# 68000_afterWireing.net
KiCad netlist of a schematic drawn in EAGLE
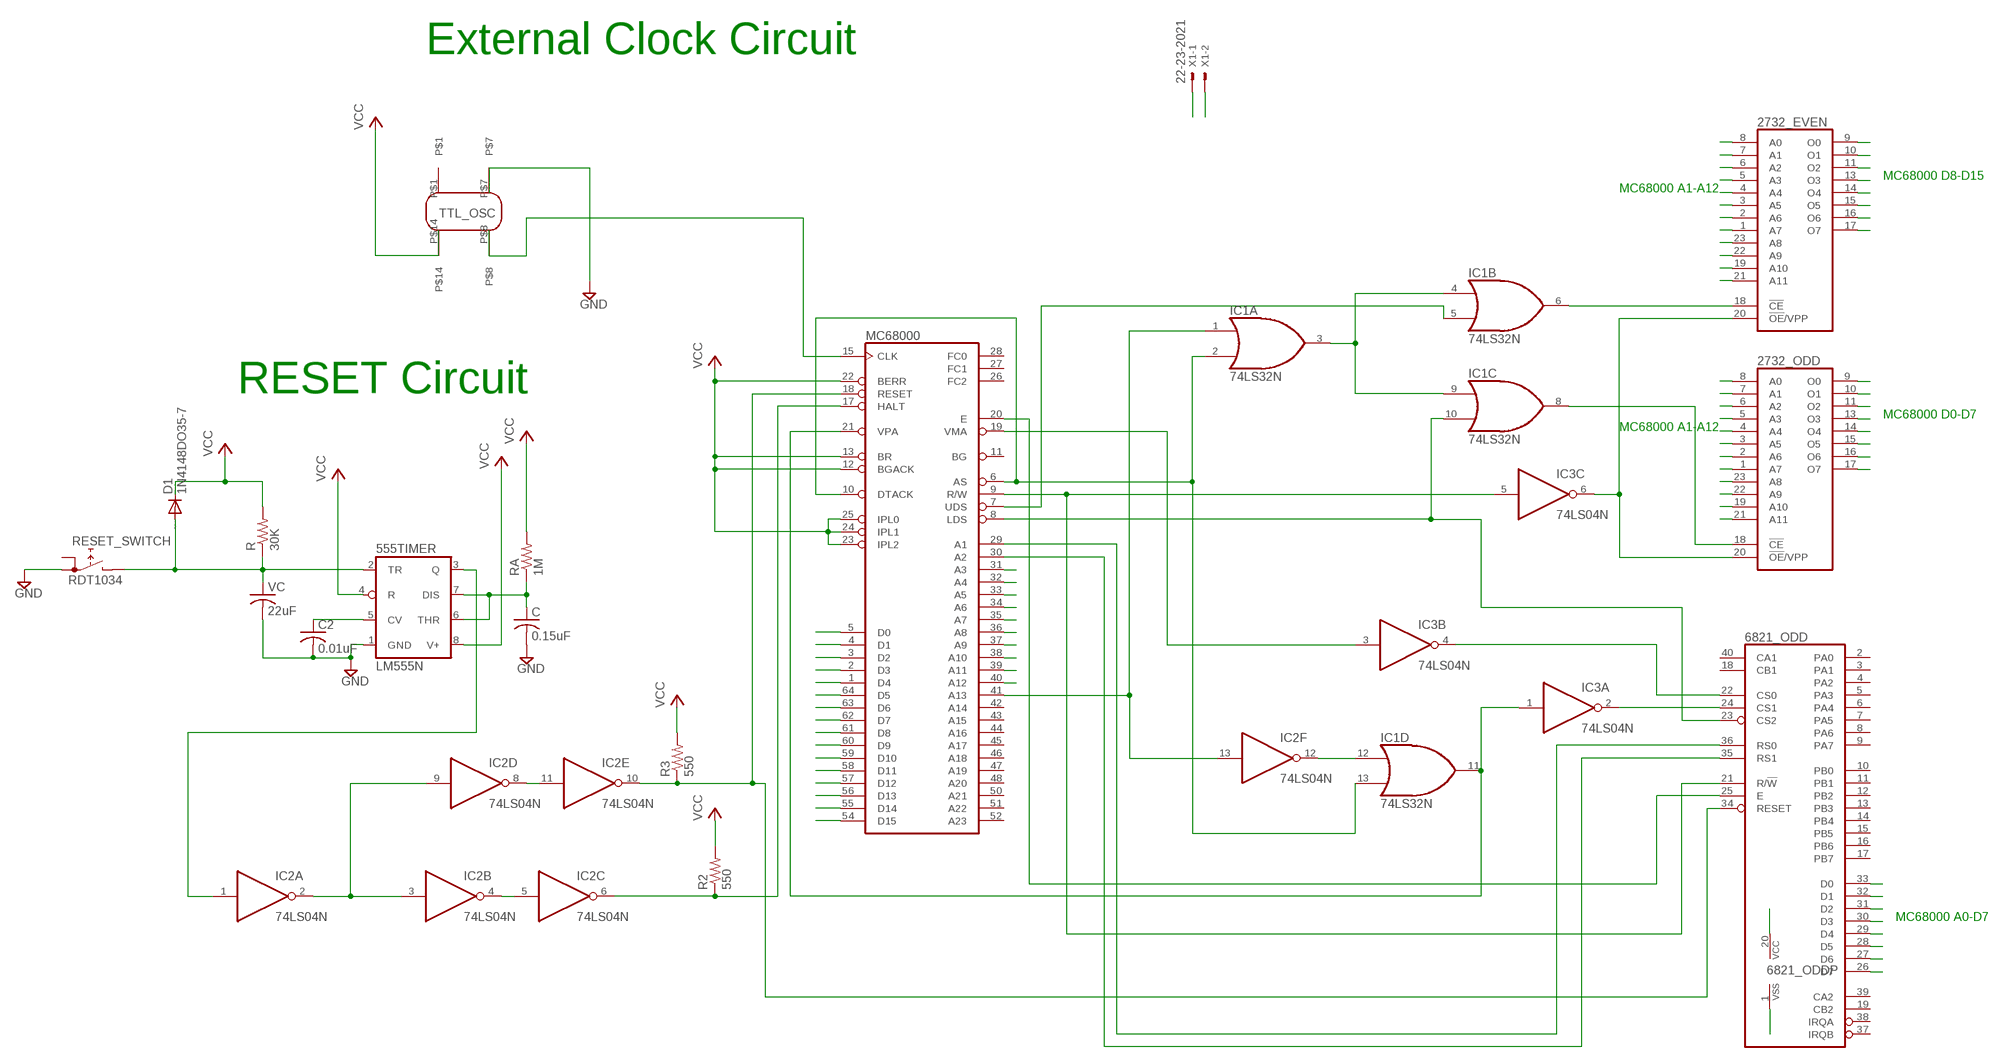
[diagram p0: schematic, sheet 1]

(export (version "E")
  (design (tool "Eeschema 10.0.6"))
  (components
    (comp (ref "555TIMER")
      (value "LM555N")
      (footprint "eagle-import:DIL08")
      (libsource (lib "eagle-import") (part "555NLM"))
    )
    (comp (ref "2732_EVEN")
      (value "2732")
      (footprint "eagle-import:DIL24")
      (libsource (lib "eagle-import") (part "2732"))
    )
    (comp (ref "2732_ODD")
      (value "2732")
      (footprint "eagle-import:DIL24")
      (libsource (lib "eagle-import") (part "2732"))
    )
    (comp (ref "6821_ODD")
      (value "6821")
      (footprint "eagle-import:DIL40")
      (fields (field (name "MF") "NTE ELECTRONICS") (field (name "MPN") "NTE6821"))
      (libsource (lib "eagle-import") (part "6821"))
    )
    (comp (ref "C")
      (value "0.15uF")
      (footprint "eagle-import:C025-024X044")
      (libsource (lib "eagle-import") (part "C-US025-024X044"))
    )
    (comp (ref "C2")
      (value "0.01uF")
      (footprint "eagle-import:C025-024X044")
      (libsource (lib "eagle-import") (part "C-US025-024X044"))
    )
    (comp (ref "D1")
      (value "1N4148DO35-7")
      (footprint "eagle-import:DO35-7")
      (libsource (lib "eagle-import") (part "1N4148DO35-7"))
    )
    (comp (ref "IC1")
      (value "74LS32N")
      (footprint "eagle-import:DIL14")
      (libsource (lib "eagle-import") (part "7432NLS"))
    )
    (comp (ref "IC2")
      (value "74LS04N")
      (footprint "eagle-import:DIL14")
      (libsource (lib "eagle-import") (part "7404NLS"))
    )
    (comp (ref "IC3")
      (value "74LS04N")
      (footprint "eagle-import:DIL14")
      (libsource (lib "eagle-import") (part "7404NLS"))
    )
    (comp (ref "MC68000")
      (value "MC68000P")
      (footprint "eagle-import:DIL64")
      (libsource (lib "eagle-import") (part "MC68000P"))
    )
    (comp (ref "R")
      (value "30K")
      (footprint "eagle-import:0204V")
      (libsource (lib "eagle-import") (part "R-US_0204/2V"))
    )
    (comp (ref "R2")
      (value "550")
      (footprint "eagle-import:0204V")
      (libsource (lib "eagle-import") (part "R-US_0204/2V"))
    )
    (comp (ref "R3")
      (value "550")
      (footprint "eagle-import:0204V")
      (libsource (lib "eagle-import") (part "R-US_0204/2V"))
    )
    (comp (ref "RA")
      (value "1M")
      (footprint "eagle-import:0204V")
      (libsource (lib "eagle-import") (part "R-US_0204/2V"))
    )
    (comp (ref "RESET_SWITCH")
      (value "RDT1034")
      (footprint "eagle-import:RDT1034")
      (libsource (lib "eagle-import") (part "RDT1034"))
    )
    (comp (ref "U$1")
      (value "TTL_OSCILLATOR")
      (footprint "eagle-import:TTL_OSCILLATOR")
      (libsource (lib "eagle-import") (part "TTL_OSCILLATOR"))
    )
    (comp (ref "VC")
      (value "22uF")
      (footprint "eagle-import:C025-024X044")
      (libsource (lib "eagle-import") (part "C-US025-024X044"))
    )
    (comp (ref "X1")
      (value "22-23-2021")
      (footprint "eagle-import:22-23-2021")
      (fields (field (name "MF") "MOLEX"))
      (libsource (lib "eagle-import") (part "22-23-2021"))
    )
  )
  (nets
    (net (code "1") (name "/A1") (class "Default")
      (node (ref "2732_EVEN") (pin "8") (pinfunction "A0_8") (pintype "input"))
      (node (ref "2732_ODD") (pin "8") (pinfunction "A0_8") (pintype "input"))
      (node (ref "6821_ODD") (pin "36") (pinfunction "RS0_36") (pintype "input"))
      (node (ref "MC68000") (pin "29") (pinfunction "A1_29") (pintype "output"))
    )
    (net (code "2") (name "/A2") (class "Default")
      (node (ref "2732_EVEN") (pin "7") (pinfunction "A1_7") (pintype "input"))
      (node (ref "2732_ODD") (pin "7") (pinfunction "A1_7") (pintype "input"))
      (node (ref "6821_ODD") (pin "35") (pinfunction "RS1_35") (pintype "input"))
      (node (ref "MC68000") (pin "30") (pinfunction "A2_30") (pintype "output"))
    )
    (net (code "3") (name "/A3") (class "Default")
      (node (ref "2732_EVEN") (pin "6") (pinfunction "A2_6") (pintype "input"))
      (node (ref "2732_ODD") (pin "6") (pinfunction "A2_6") (pintype "input"))
      (node (ref "MC68000") (pin "31") (pinfunction "A3_31") (pintype "output"))
    )
    (net (code "4") (name "/A4") (class "Default")
      (node (ref "2732_EVEN") (pin "5") (pinfunction "A3_5") (pintype "input"))
      (node (ref "2732_ODD") (pin "5") (pinfunction "A3_5") (pintype "input"))
      (node (ref "MC68000") (pin "32") (pinfunction "A4_32") (pintype "output"))
    )
    (net (code "5") (name "/A5") (class "Default")
      (node (ref "2732_EVEN") (pin "4") (pinfunction "A4_4") (pintype "input"))
      (node (ref "2732_ODD") (pin "4") (pinfunction "A4_4") (pintype "input"))
      (node (ref "MC68000") (pin "33") (pinfunction "A5_33") (pintype "output"))
    )
    (net (code "6") (name "/A6") (class "Default")
      (node (ref "2732_EVEN") (pin "3") (pinfunction "A5_3") (pintype "input"))
      (node (ref "2732_ODD") (pin "3") (pinfunction "A5_3") (pintype "input"))
      (node (ref "MC68000") (pin "34") (pinfunction "A6_34") (pintype "output"))
    )
    (net (code "7") (name "/A7") (class "Default")
      (node (ref "2732_EVEN") (pin "2") (pinfunction "A6_2") (pintype "input"))
      (node (ref "2732_ODD") (pin "2") (pinfunction "A6_2") (pintype "input"))
      (node (ref "MC68000") (pin "35") (pinfunction "A7_35") (pintype "output"))
    )
    (net (code "8") (name "/A8") (class "Default")
      (node (ref "2732_EVEN") (pin "1") (pinfunction "A7_1") (pintype "input"))
      (node (ref "2732_ODD") (pin "1") (pinfunction "A7_1") (pintype "input"))
      (node (ref "MC68000") (pin "36") (pinfunction "A8_36") (pintype "output"))
    )
    (net (code "9") (name "/A9") (class "Default")
      (node (ref "2732_EVEN") (pin "23") (pinfunction "A8_23") (pintype "input"))
      (node (ref "2732_ODD") (pin "23") (pinfunction "A8_23") (pintype "input"))
      (node (ref "MC68000") (pin "37") (pinfunction "A9_37") (pintype "output"))
    )
    (net (code "10") (name "/A10") (class "Default")
      (node (ref "2732_EVEN") (pin "22") (pinfunction "A9_22") (pintype "input"))
      (node (ref "2732_ODD") (pin "22") (pinfunction "A9_22") (pintype "input"))
      (node (ref "MC68000") (pin "38") (pinfunction "A10_38") (pintype "output"))
    )
    (net (code "11") (name "/A11") (class "Default")
      (node (ref "2732_EVEN") (pin "19") (pinfunction "A10_19") (pintype "input"))
      (node (ref "2732_ODD") (pin "19") (pinfunction "A10_19") (pintype "input"))
      (node (ref "MC68000") (pin "39") (pinfunction "A11_39") (pintype "output"))
    )
    (net (code "12") (name "/A12") (class "Default")
      (node (ref "2732_EVEN") (pin "21") (pinfunction "A11_21") (pintype "input"))
      (node (ref "2732_ODD") (pin "21") (pinfunction "A11_21") (pintype "input"))
      (node (ref "MC68000") (pin "40") (pinfunction "A12_40") (pintype "output"))
    )
    (net (code "13") (name "/D0") (class "Default")
      (node (ref "2732_ODD") (pin "9") (pinfunction "O0_9") (pintype "tri_state"))
      (node (ref "6821_ODD") (pin "33") (pinfunction "D0_33") (pintype "bidirectional"))
      (node (ref "MC68000") (pin "5") (pinfunction "D0_5") (pintype "bidirectional"))
    )
    (net (code "14") (name "/D1") (class "Default")
      (node (ref "2732_ODD") (pin "10") (pinfunction "O1_10") (pintype "tri_state"))
      (node (ref "6821_ODD") (pin "32") (pinfunction "D1_32") (pintype "bidirectional"))
      (node (ref "MC68000") (pin "4") (pinfunction "D1_4") (pintype "bidirectional"))
    )
    (net (code "15") (name "/D2") (class "Default")
      (node (ref "2732_ODD") (pin "11") (pinfunction "O2_11") (pintype "tri_state"))
      (node (ref "6821_ODD") (pin "31") (pinfunction "D2_31") (pintype "bidirectional"))
      (node (ref "MC68000") (pin "3") (pinfunction "D2_3") (pintype "bidirectional"))
    )
    (net (code "16") (name "/D3") (class "Default")
      (node (ref "2732_ODD") (pin "13") (pinfunction "O3_13") (pintype "tri_state"))
      (node (ref "6821_ODD") (pin "30") (pinfunction "D3_30") (pintype "bidirectional"))
      (node (ref "MC68000") (pin "2") (pinfunction "D3_2") (pintype "bidirectional"))
    )
    (net (code "17") (name "/D4") (class "Default")
      (node (ref "2732_ODD") (pin "14") (pinfunction "O4_14") (pintype "tri_state"))
      (node (ref "6821_ODD") (pin "29") (pinfunction "D4_29") (pintype "bidirectional"))
      (node (ref "MC68000") (pin "1") (pinfunction "D4_1") (pintype "bidirectional"))
    )
    (net (code "18") (name "/D5") (class "Default")
      (node (ref "2732_ODD") (pin "15") (pinfunction "O5_15") (pintype "tri_state"))
      (node (ref "6821_ODD") (pin "28") (pinfunction "D5_28") (pintype "bidirectional"))
      (node (ref "MC68000") (pin "64") (pinfunction "D5_64") (pintype "bidirectional"))
    )
    (net (code "19") (name "/D6") (class "Default")
      (node (ref "2732_ODD") (pin "16") (pinfunction "O6_16") (pintype "tri_state"))
      (node (ref "6821_ODD") (pin "27") (pinfunction "D6_27") (pintype "bidirectional"))
      (node (ref "MC68000") (pin "63") (pinfunction "D6_63") (pintype "bidirectional"))
    )
    (net (code "20") (name "/D7") (class "Default")
      (node (ref "2732_ODD") (pin "17") (pinfunction "O7_17") (pintype "tri_state"))
      (node (ref "6821_ODD") (pin "26") (pinfunction "D7_26") (pintype "bidirectional"))
      (node (ref "MC68000") (pin "62") (pinfunction "D7_62") (pintype "bidirectional"))
    )
    (net (code "21") (name "/D8") (class "Default")
      (node (ref "2732_EVEN") (pin "9") (pinfunction "O0_9") (pintype "tri_state"))
      (node (ref "MC68000") (pin "61") (pinfunction "D8_61") (pintype "bidirectional"))
    )
    (net (code "22") (name "/D9") (class "Default")
      (node (ref "2732_EVEN") (pin "10") (pinfunction "O1_10") (pintype "tri_state"))
      (node (ref "MC68000") (pin "60") (pinfunction "D9_60") (pintype "bidirectional"))
    )
    (net (code "23") (name "/D10") (class "Default")
      (node (ref "2732_EVEN") (pin "11") (pinfunction "O2_11") (pintype "tri_state"))
      (node (ref "MC68000") (pin "59") (pinfunction "D10_59") (pintype "bidirectional"))
    )
    (net (code "24") (name "/D11") (class "Default")
      (node (ref "2732_EVEN") (pin "13") (pinfunction "O3_13") (pintype "tri_state"))
      (node (ref "MC68000") (pin "58") (pinfunction "D11_58") (pintype "bidirectional"))
    )
    (net (code "25") (name "/D12") (class "Default")
      (node (ref "2732_EVEN") (pin "14") (pinfunction "O4_14") (pintype "tri_state"))
      (node (ref "MC68000") (pin "57") (pinfunction "D12_57") (pintype "bidirectional"))
    )
    (net (code "26") (name "/D13") (class "Default")
      (node (ref "2732_EVEN") (pin "15") (pinfunction "O5_15") (pintype "tri_state"))
      (node (ref "MC68000") (pin "56") (pinfunction "D13_56") (pintype "bidirectional"))
    )
    (net (code "27") (name "/D14") (class "Default")
      (node (ref "2732_EVEN") (pin "16") (pinfunction "O6_16") (pintype "tri_state"))
      (node (ref "MC68000") (pin "55") (pinfunction "D14_55") (pintype "bidirectional"))
    )
    (net (code "28") (name "/D15") (class "Default")
      (node (ref "2732_EVEN") (pin "17") (pinfunction "O7_17") (pintype "tri_state"))
      (node (ref "MC68000") (pin "54") (pinfunction "D15_54") (pintype "bidirectional"))
    )
    (net (code "29") (name "GND") (class "Default")
      (node (ref "555TIMER") (pin "1") (pinfunction "GND_1") (pintype "power_in"))
      (node (ref "6821_ODD") (pin "1") (pinfunction "VSS_1") (pintype "power_in"))
      (node (ref "C") (pin "2") (pinfunction "2_2") (pintype "passive"))
      (node (ref "C2") (pin "2") (pinfunction "2_2") (pintype "passive"))
      (node (ref "RESET_SWITCH") (pin "A1") (pinfunction "A1_A1") (pintype "passive"))
      (node (ref "U$1") (pin "P$7") (pinfunction "P$7_P$7") (pintype "bidirectional"))
      (node (ref "VC") (pin "2") (pinfunction "2_2") (pintype "passive"))
      (node (ref "X1") (pin "2") (pinfunction "S_2") (pintype "passive"))
    )
    (net (code "30") (name "Net-(555TIMER-CV)") (class "Default")
      (node (ref "555TIMER") (pin "5") (pinfunction "CV_5") (pintype "input"))
      (node (ref "C2") (pin "1") (pinfunction "1_1") (pintype "passive"))
    )
    (net (code "31") (name "Net-(555TIMER-DIS)") (class "Default")
      (node (ref "555TIMER") (pin "6") (pinfunction "THR_6") (pintype "input"))
      (node (ref "555TIMER") (pin "7") (pinfunction "DIS_7") (pintype "input"))
      (node (ref "C") (pin "1") (pinfunction "1_1") (pintype "passive"))
      (node (ref "RA") (pin "1") (pinfunction "1_1") (pintype "passive"))
    )
    (net (code "32") (name "Net-(555TIMER-Q)") (class "Default")
      (node (ref "555TIMER") (pin "3") (pinfunction "Q_3") (pintype "output"))
      (node (ref "IC2") (pin "1") (pinfunction "I_1") (pintype "input"))
    )
    (net (code "33") (name "Net-(555TIMER-TR)") (class "Default")
      (node (ref "555TIMER") (pin "2") (pinfunction "TR_2") (pintype "input"))
      (node (ref "D1") (pin "A") (pinfunction "A_A") (pintype "passive"))
      (node (ref "R") (pin "1") (pinfunction "1_1") (pintype "passive"))
      (node (ref "RESET_SWITCH") (pin "B") (pinfunction "B_B") (pintype "passive"))
      (node (ref "VC") (pin "1") (pinfunction "1_1") (pintype "passive"))
    )
    (net (code "34") (name "Net-(2732_EVENA-~{CE})") (class "Default")
      (node (ref "2732_EVEN") (pin "18") (pinfunction "~{CE}_18") (pintype "input"))
      (node (ref "IC1") (pin "6") (pinfunction "O_6") (pintype "output"))
    )
    (net (code "35") (name "Net-(2732_EVENA-~{OE}{slash}VPP)") (class "Default")
      (node (ref "2732_EVEN") (pin "20") (pinfunction "~{OE}/VPP_20") (pintype "input"))
      (node (ref "2732_ODD") (pin "20") (pinfunction "~{OE}/VPP_20") (pintype "input"))
      (node (ref "IC3") (pin "6") (pinfunction "O_6") (pintype "output"))
    )
    (net (code "36") (name "Net-(2732_ODDA-~{CE})") (class "Default")
      (node (ref "2732_ODD") (pin "18") (pinfunction "~{CE}_18") (pintype "input"))
      (node (ref "IC1") (pin "8") (pinfunction "O_8") (pintype "output"))
    )
    (net (code "37") (name "Net-(6821_ODDA-CS0)") (class "Default")
      (node (ref "6821_ODD") (pin "22") (pinfunction "CS0_22") (pintype "input"))
      (node (ref "IC3") (pin "4") (pinfunction "O_4") (pintype "output"))
    )
    (net (code "38") (name "Net-(6821_ODDA-CS1)") (class "Default")
      (node (ref "6821_ODD") (pin "24") (pinfunction "CS1_24") (pintype "input"))
      (node (ref "IC3") (pin "2") (pinfunction "O_2") (pintype "output"))
    )
    (net (code "39") (name "Net-(6821_ODDA-CS2)") (class "Default")
      (node (ref "6821_ODD") (pin "23") (pinfunction "CS2_23") (pintype "input"))
      (node (ref "IC1") (pin "10") (pinfunction "I1_10") (pintype "input"))
      (node (ref "MC68000") (pin "8") (pinfunction "LDS_8") (pintype "output"))
    )
    (net (code "40") (name "Net-(6821_ODDA-E)") (class "Default")
      (node (ref "6821_ODD") (pin "25") (pinfunction "E_25") (pintype "input"))
      (node (ref "MC68000") (pin "20") (pinfunction "E_20") (pintype "output"))
    )
    (net (code "41") (name "Net-(6821_ODDA-RESET)") (class "Default")
      (node (ref "6821_ODD") (pin "34") (pinfunction "RESET_34") (pintype "input"))
      (node (ref "IC2") (pin "10") (pinfunction "O_10") (pintype "output"))
      (node (ref "MC68000") (pin "18") (pinfunction "RESET_18") (pintype "bidirectional"))
      (node (ref "R3") (pin "1") (pinfunction "1_1") (pintype "passive"))
    )
    (net (code "42") (name "Net-(6821_ODDA-R{slash}~{W})") (class "Default")
      (node (ref "6821_ODD") (pin "21") (pinfunction "R/~{W}_21") (pintype "input"))
      (node (ref "IC3") (pin "5") (pinfunction "I_5") (pintype "input"))
      (node (ref "MC68000") (pin "9") (pinfunction "R/W_9") (pintype "output"))
    )
    (net (code "43") (name "Net-(IC1A-I0)") (class "Default")
      (node (ref "IC1") (pin "1") (pinfunction "I0_1") (pintype "input"))
      (node (ref "IC2") (pin "13") (pinfunction "I_13") (pintype "input"))
      (node (ref "MC68000") (pin "41") (pinfunction "A13_41") (pintype "output"))
    )
    (net (code "44") (name "Net-(IC1A-I1)") (class "Default")
      (node (ref "IC1") (pin "13") (pinfunction "I1_13") (pintype "input"))
      (node (ref "IC1") (pin "2") (pinfunction "I1_2") (pintype "input"))
      (node (ref "MC68000") (pin "10") (pinfunction "DTACK_10") (pintype "input"))
      (node (ref "MC68000") (pin "6") (pinfunction "AS_6") (pintype "output"))
    )
    (net (code "45") (name "Net-(IC1A-O)") (class "Default")
      (node (ref "IC1") (pin "3") (pinfunction "O_3") (pintype "output"))
      (node (ref "IC1") (pin "4") (pinfunction "I0_4") (pintype "input"))
      (node (ref "IC1") (pin "9") (pinfunction "I0_9") (pintype "input"))
    )
    (net (code "46") (name "Net-(IC1B-I1)") (class "Default")
      (node (ref "IC1") (pin "5") (pinfunction "I1_5") (pintype "input"))
      (node (ref "MC68000") (pin "7") (pinfunction "UDS_7") (pintype "output"))
    )
    (net (code "47") (name "Net-(IC1D-I0)") (class "Default")
      (node (ref "IC1") (pin "12") (pinfunction "I0_12") (pintype "input"))
      (node (ref "IC2") (pin "12") (pinfunction "O_12") (pintype "output"))
    )
    (net (code "48") (name "Net-(IC1D-O)") (class "Default")
      (node (ref "IC1") (pin "11") (pinfunction "O_11") (pintype "output"))
      (node (ref "IC3") (pin "1") (pinfunction "I_1") (pintype "input"))
      (node (ref "MC68000") (pin "21") (pinfunction "VPA_21") (pintype "input"))
    )
    (net (code "49") (name "Net-(IC2A-O)") (class "Default")
      (node (ref "IC2") (pin "2") (pinfunction "O_2") (pintype "output"))
      (node (ref "IC2") (pin "3") (pinfunction "I_3") (pintype "input"))
      (node (ref "IC2") (pin "9") (pinfunction "I_9") (pintype "input"))
    )
    (net (code "50") (name "Net-(IC2B-O)") (class "Default")
      (node (ref "IC2") (pin "4") (pinfunction "O_4") (pintype "output"))
      (node (ref "IC2") (pin "5") (pinfunction "I_5") (pintype "input"))
    )
    (net (code "51") (name "Net-(IC2C-O)") (class "Default")
      (node (ref "IC2") (pin "6") (pinfunction "O_6") (pintype "output"))
      (node (ref "MC68000") (pin "17") (pinfunction "HALT_17") (pintype "bidirectional"))
      (node (ref "R2") (pin "1") (pinfunction "1_1") (pintype "passive"))
    )
    (net (code "52") (name "Net-(IC2D-O)") (class "Default")
      (node (ref "IC2") (pin "11") (pinfunction "I_11") (pintype "input"))
      (node (ref "IC2") (pin "8") (pinfunction "O_8") (pintype "output"))
    )
    (net (code "53") (name "Net-(IC3B-I)") (class "Default")
      (node (ref "IC3") (pin "3") (pinfunction "I_3") (pintype "input"))
      (node (ref "MC68000") (pin "19") (pinfunction "VMA_19") (pintype "output"))
    )
    (net (code "54") (name "Net-(MC68000A-CLK)") (class "Default")
      (node (ref "MC68000") (pin "15") (pinfunction "CLK_15") (pintype "input"))
      (node (ref "U$1") (pin "P$8") (pinfunction "P$8_P$8") (pintype "bidirectional"))
    )
    (net (code "55") (name "VCC") (class "Default")
      (node (ref "555TIMER") (pin "4") (pinfunction "R_4") (pintype "input"))
      (node (ref "555TIMER") (pin "8") (pinfunction "V+_8") (pintype "power_in"))
      (node (ref "6821_ODD") (pin "20") (pinfunction "VCC_20") (pintype "power_in"))
      (node (ref "D1") (pin "C") (pinfunction "C_C") (pintype "passive"))
      (node (ref "MC68000") (pin "12") (pinfunction "BGACK_12") (pintype "input"))
      (node (ref "MC68000") (pin "13") (pinfunction "BR_13") (pintype "input"))
      (node (ref "MC68000") (pin "22") (pinfunction "BERR_22") (pintype "input"))
      (node (ref "MC68000") (pin "23") (pinfunction "IPL2_23") (pintype "input"))
      (node (ref "MC68000") (pin "24") (pinfunction "IPL1_24") (pintype "input"))
      (node (ref "MC68000") (pin "25") (pinfunction "IPL0_25") (pintype "input"))
      (node (ref "R") (pin "2") (pinfunction "2_2") (pintype "passive"))
      (node (ref "R2") (pin "2") (pinfunction "2_2") (pintype "passive"))
      (node (ref "R3") (pin "2") (pinfunction "2_2") (pintype "passive"))
      (node (ref "RA") (pin "2") (pinfunction "2_2") (pintype "passive"))
      (node (ref "U$1") (pin "P$14") (pinfunction "P$14_P$14") (pintype "bidirectional"))
      (node (ref "X1") (pin "1") (pinfunction "S_1") (pintype "passive"))
    )
    (net (code "56") (name "unconnected-(6821_ODDA-CA1-Pad40)") (class "Default")
      (node (ref "6821_ODD") (pin "40") (pinfunction "CA1_40") (pintype "input"))
    )
    (net (code "57") (name "unconnected-(6821_ODDA-CA2-Pad39)") (class "Default")
      (node (ref "6821_ODD") (pin "39") (pinfunction "CA2_39") (pintype "bidirectional"))
    )
    (net (code "58") (name "unconnected-(6821_ODDA-CB1-Pad18)") (class "Default")
      (node (ref "6821_ODD") (pin "18") (pinfunction "CB1_18") (pintype "input"))
    )
    (net (code "59") (name "unconnected-(6821_ODDA-CB2-Pad19)") (class "Default")
      (node (ref "6821_ODD") (pin "19") (pinfunction "CB2_19") (pintype "bidirectional"))
    )
    (net (code "60") (name "unconnected-(6821_ODDA-IRQA-Pad38)") (class "Default")
      (node (ref "6821_ODD") (pin "38") (pinfunction "IRQA_38") (pintype "open_collector"))
    )
    (net (code "61") (name "unconnected-(6821_ODDA-IRQB-Pad37)") (class "Default")
      (node (ref "6821_ODD") (pin "37") (pinfunction "IRQB_37") (pintype "open_collector"))
    )
    (net (code "62") (name "unconnected-(6821_ODDA-PA0-Pad2)") (class "Default")
      (node (ref "6821_ODD") (pin "2") (pinfunction "PA0_2") (pintype "bidirectional"))
    )
    (net (code "63") (name "unconnected-(6821_ODDA-PA1-Pad3)") (class "Default")
      (node (ref "6821_ODD") (pin "3") (pinfunction "PA1_3") (pintype "bidirectional"))
    )
    (net (code "64") (name "unconnected-(6821_ODDA-PA2-Pad4)") (class "Default")
      (node (ref "6821_ODD") (pin "4") (pinfunction "PA2_4") (pintype "bidirectional"))
    )
    (net (code "65") (name "unconnected-(6821_ODDA-PA3-Pad5)") (class "Default")
      (node (ref "6821_ODD") (pin "5") (pinfunction "PA3_5") (pintype "bidirectional"))
    )
    (net (code "66") (name "unconnected-(6821_ODDA-PA4-Pad6)") (class "Default")
      (node (ref "6821_ODD") (pin "6") (pinfunction "PA4_6") (pintype "bidirectional"))
    )
    (net (code "67") (name "unconnected-(6821_ODDA-PA5-Pad7)") (class "Default")
      (node (ref "6821_ODD") (pin "7") (pinfunction "PA5_7") (pintype "bidirectional"))
    )
    (net (code "68") (name "unconnected-(6821_ODDA-PA6-Pad8)") (class "Default")
      (node (ref "6821_ODD") (pin "8") (pinfunction "PA6_8") (pintype "bidirectional"))
    )
    (net (code "69") (name "unconnected-(6821_ODDA-PA7-Pad9)") (class "Default")
      (node (ref "6821_ODD") (pin "9") (pinfunction "PA7_9") (pintype "bidirectional"))
    )
    (net (code "70") (name "unconnected-(6821_ODDA-PB0-Pad10)") (class "Default")
      (node (ref "6821_ODD") (pin "10") (pinfunction "PB0_10") (pintype "bidirectional"))
    )
    (net (code "71") (name "unconnected-(6821_ODDA-PB1-Pad11)") (class "Default")
      (node (ref "6821_ODD") (pin "11") (pinfunction "PB1_11") (pintype "bidirectional"))
    )
    (net (code "72") (name "unconnected-(6821_ODDA-PB2-Pad12)") (class "Default")
      (node (ref "6821_ODD") (pin "12") (pinfunction "PB2_12") (pintype "bidirectional"))
    )
    (net (code "73") (name "unconnected-(6821_ODDA-PB3-Pad13)") (class "Default")
      (node (ref "6821_ODD") (pin "13") (pinfunction "PB3_13") (pintype "bidirectional"))
    )
    (net (code "74") (name "unconnected-(6821_ODDA-PB4-Pad14)") (class "Default")
      (node (ref "6821_ODD") (pin "14") (pinfunction "PB4_14") (pintype "bidirectional"))
    )
    (net (code "75") (name "unconnected-(6821_ODDA-PB5-Pad15)") (class "Default")
      (node (ref "6821_ODD") (pin "15") (pinfunction "PB5_15") (pintype "bidirectional"))
    )
    (net (code "76") (name "unconnected-(6821_ODDA-PB6-Pad16)") (class "Default")
      (node (ref "6821_ODD") (pin "16") (pinfunction "PB6_16") (pintype "bidirectional"))
    )
    (net (code "77") (name "unconnected-(6821_ODDA-PB7-Pad17)") (class "Default")
      (node (ref "6821_ODD") (pin "17") (pinfunction "PB7_17") (pintype "bidirectional"))
    )
    (net (code "78") (name "unconnected-(MC68000A-A14-Pad42)") (class "Default")
      (node (ref "MC68000") (pin "42") (pinfunction "A14_42") (pintype "output"))
    )
    (net (code "79") (name "unconnected-(MC68000A-A15-Pad43)") (class "Default")
      (node (ref "MC68000") (pin "43") (pinfunction "A15_43") (pintype "output"))
    )
    (net (code "80") (name "unconnected-(MC68000A-A16-Pad44)") (class "Default")
      (node (ref "MC68000") (pin "44") (pinfunction "A16_44") (pintype "output"))
    )
    (net (code "81") (name "unconnected-(MC68000A-A17-Pad45)") (class "Default")
      (node (ref "MC68000") (pin "45") (pinfunction "A17_45") (pintype "output"))
    )
    (net (code "82") (name "unconnected-(MC68000A-A18-Pad46)") (class "Default")
      (node (ref "MC68000") (pin "46") (pinfunction "A18_46") (pintype "output"))
    )
    (net (code "83") (name "unconnected-(MC68000A-A19-Pad47)") (class "Default")
      (node (ref "MC68000") (pin "47") (pinfunction "A19_47") (pintype "output"))
    )
    (net (code "84") (name "unconnected-(MC68000A-A20-Pad48)") (class "Default")
      (node (ref "MC68000") (pin "48") (pinfunction "A20_48") (pintype "output"))
    )
    (net (code "85") (name "unconnected-(MC68000A-A21-Pad50)") (class "Default")
      (node (ref "MC68000") (pin "50") (pinfunction "A21_50") (pintype "output"))
    )
    (net (code "86") (name "unconnected-(MC68000A-A22-Pad51)") (class "Default")
      (node (ref "MC68000") (pin "51") (pinfunction "A22_51") (pintype "output"))
    )
    (net (code "87") (name "unconnected-(MC68000A-A23-Pad52)") (class "Default")
      (node (ref "MC68000") (pin "52") (pinfunction "A23_52") (pintype "output"))
    )
    (net (code "88") (name "unconnected-(MC68000A-BG-Pad11)") (class "Default")
      (node (ref "MC68000") (pin "11") (pinfunction "BG_11") (pintype "output"))
    )
    (net (code "89") (name "unconnected-(MC68000A-FC0-Pad28)") (class "Default")
      (node (ref "MC68000") (pin "28") (pinfunction "FC0_28") (pintype "output"))
    )
    (net (code "90") (name "unconnected-(MC68000A-FC1-Pad27)") (class "Default")
      (node (ref "MC68000") (pin "27") (pinfunction "FC1_27") (pintype "output"))
    )
    (net (code "91") (name "unconnected-(MC68000A-FC2-Pad26)") (class "Default")
      (node (ref "MC68000") (pin "26") (pinfunction "FC2_26") (pintype "output"))
    )
    (net (code "92") (name "unconnected-(RESET_SWITCH-PadA)") (class "Default")
      (node (ref "RESET_SWITCH") (pin "A") (pinfunction "A_A") (pintype "passive"))
    )
    (net (code "93") (name "unconnected-(U$1-PadP$1)") (class "Default")
      (node (ref "U$1") (pin "P$1") (pinfunction "P$1_P$1") (pintype "bidirectional"))
    )
  )
)
